# ZigBee.net
KiCad netlist of a schematic drawn in Altium Designer
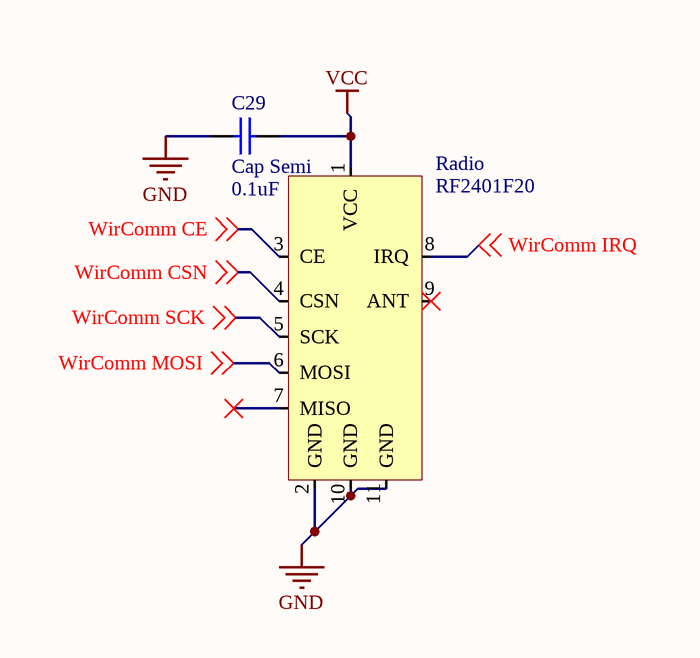
[diagram p0: ZigBee.SchDoc]

(export (version "E")
  (design (tool "Eeschema 10.0.6"))
  (components
    (comp (ref "C29")
      (value "Cap Semi")
      (footprint "1608[0603]")
      (description "Capacitor (Semiconductor SIM Model)")
      (fields (field (name "ALTIUM_VALUE") "0.1uF") (field (name "PUBLISHER") "Altium Limited"))
      (libsource (lib "Miscellaneous Devices") (part "Cap Semi"))
    )
    (comp (ref "Radio")
      (value "RF2401F20")
      (footprint "RF2401F20")
      (libsource (lib "HGCDLibrary") (part "RF2401F20"))
    )
  )
  (nets
    (net (code "1") (name "GND") (class "Default")
      (node (ref "C29") (pin "2") (pinfunction "2_2") (pintype "passive"))
      (node (ref "Radio") (pin "10") (pinfunction "GND_10") (pintype "passive"))
      (node (ref "Radio") (pin "11") (pinfunction "GND_11") (pintype "passive"))
      (node (ref "Radio") (pin "2") (pinfunction "GND_2") (pintype "passive"))
    )
    (net (code "2") (name "VCC") (class "Default")
      (node (ref "C29") (pin "1") (pinfunction "1_1") (pintype "passive"))
      (node (ref "Radio") (pin "1") (pinfunction "VCC_1") (pintype "passive"))
    )
    (net (code "3") (name "WirComm CE") (class "Default")
      (node (ref "Radio") (pin "3") (pinfunction "CE_3") (pintype "input"))
    )
    (net (code "4") (name "WirComm CSN") (class "Default")
      (node (ref "Radio") (pin "4") (pinfunction "CSN_4") (pintype "input"))
    )
    (net (code "5") (name "WirComm IRQ") (class "Default")
      (node (ref "Radio") (pin "8") (pinfunction "IRQ_8") (pintype "output"))
    )
    (net (code "6") (name "WirComm MOSI") (class "Default")
      (node (ref "Radio") (pin "6") (pinfunction "MOSI_6") (pintype "bidirectional"))
    )
    (net (code "7") (name "WirComm SCK") (class "Default")
      (node (ref "Radio") (pin "5") (pinfunction "SCK_5") (pintype "bidirectional"))
    )
    (net (code "8") (name "unconnected-(Radio-ANT-Pad9)") (class "Default")
      (node (ref "Radio") (pin "9") (pinfunction "ANT_9") (pintype "output+no_connect"))
    )
    (net (code "9") (name "unconnected-(Radio-MISO-Pad7)") (class "Default")
      (node (ref "Radio") (pin "7") (pinfunction "MISO_7") (pintype "bidirectional+no_connect"))
    )
  )
)
